# Power_And_Voltage_Shifters.net
KiCad netlist of a schematic drawn in Altium Designer
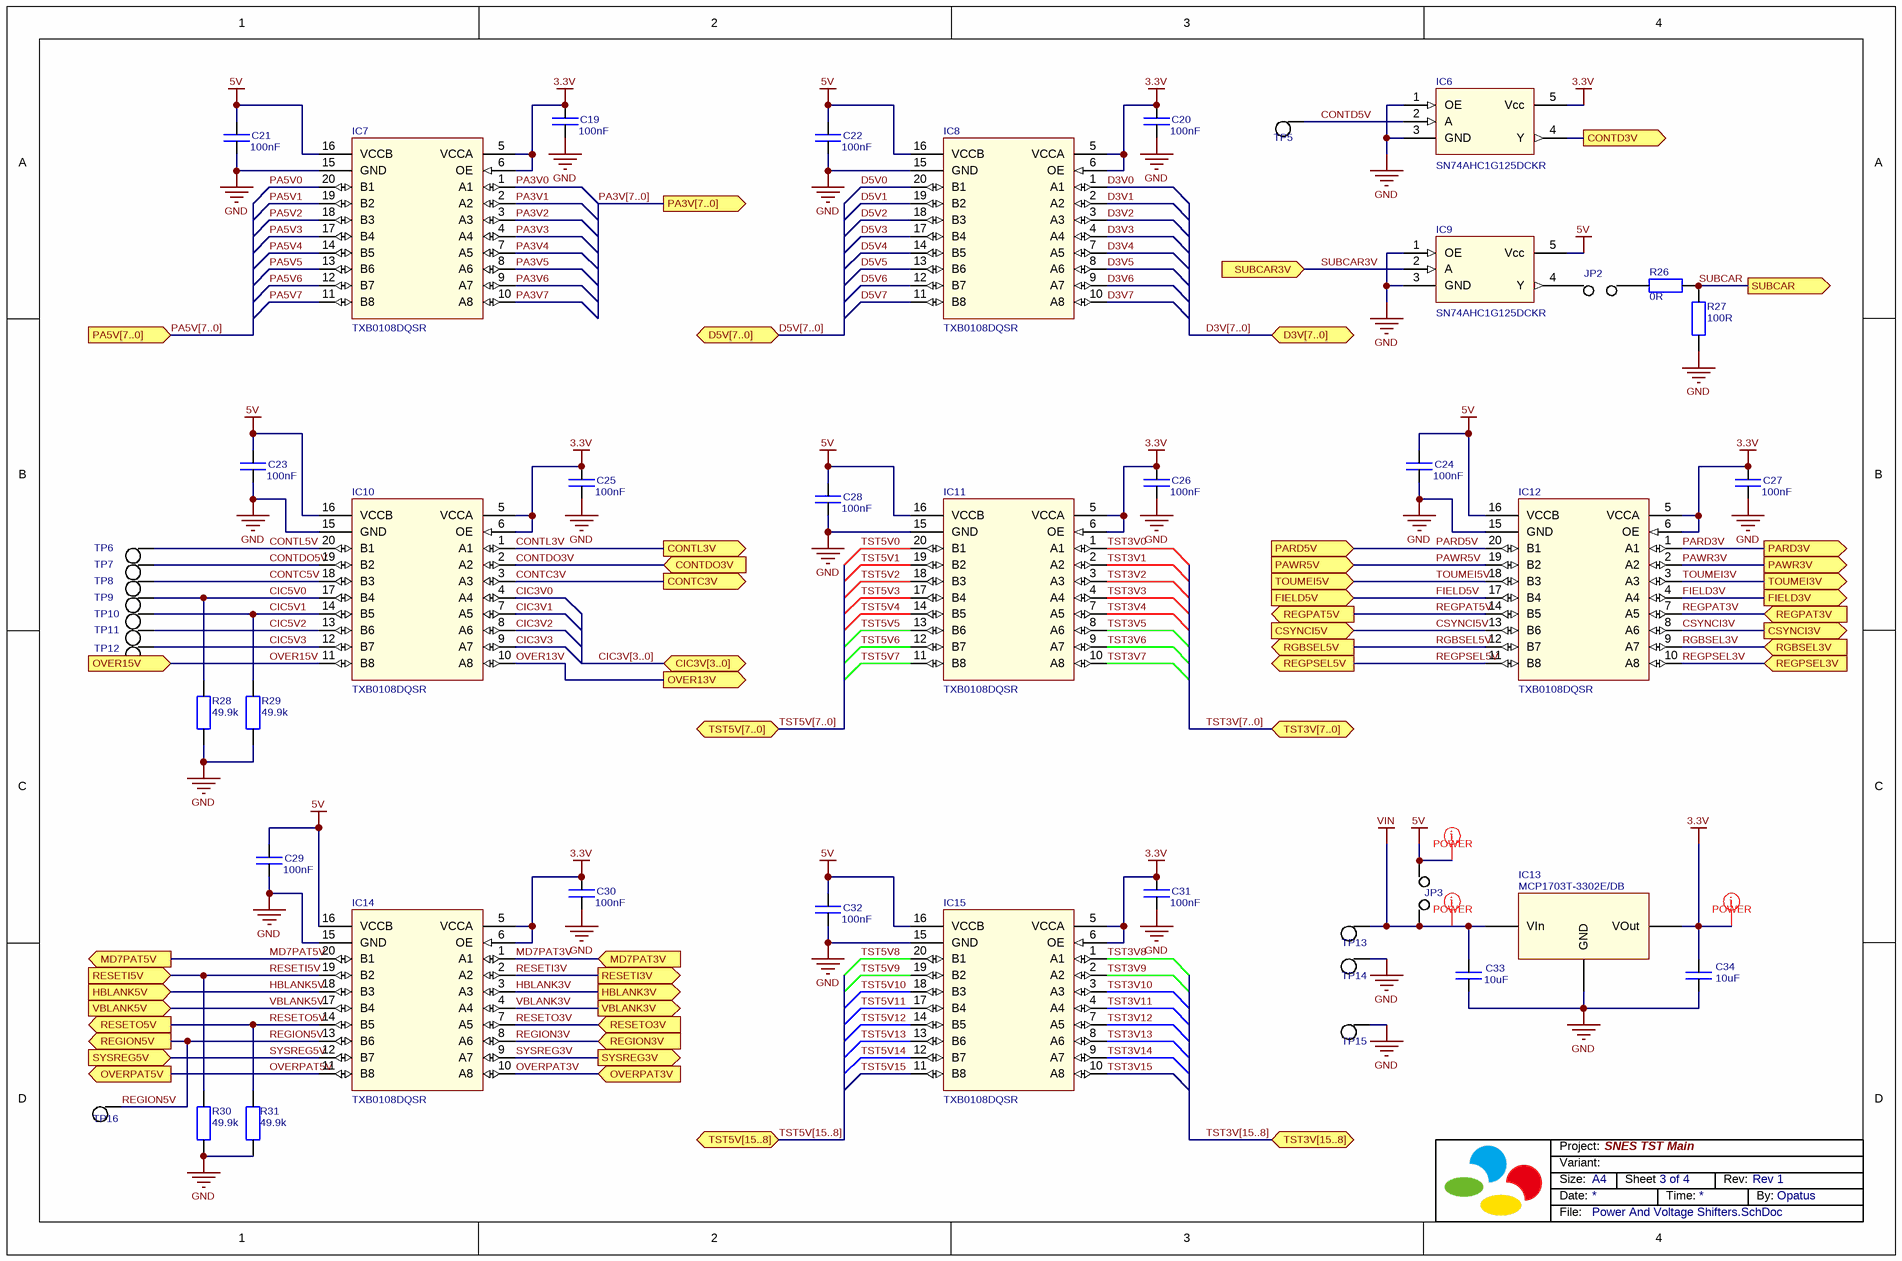
[diagram p0: Power And Voltage Shifters.SchDoc]

(export (version "E")
  (design (tool "Eeschema 10.0.6"))
  (components
    (comp (ref "C19")
      (value "100nF")
      (footprint "Cap_0402_Chip")
      (fields
        (field (name "TOLERANCE") "±20%")
        (field (name "Comment") "Ceramic Capacitor 100nF 10V ±20% X7R 0402")
      )
      (libsource (lib "PCB") (part "Capacitor"))
    )
    (comp (ref "C20")
      (value "100nF")
      (footprint "Cap_0402_Chip")
      (fields
        (field (name "TOLERANCE") "±20%")
        (field (name "Comment") "Ceramic Capacitor 100nF 10V ±20% X7R 0402")
      )
      (libsource (lib "PCB") (part "Capacitor"))
    )
    (comp (ref "C21")
      (value "100nF")
      (footprint "Cap_0402_Chip")
      (fields
        (field (name "TOLERANCE") "±20%")
        (field (name "Comment") "Ceramic Capacitor 100nF 10V ±20% X7R 0402")
      )
      (libsource (lib "PCB") (part "Capacitor"))
    )
    (comp (ref "C22")
      (value "100nF")
      (footprint "Cap_0402_Chip")
      (fields
        (field (name "TOLERANCE") "±20%")
        (field (name "Comment") "Ceramic Capacitor 100nF 10V ±20% X7R 0402")
      )
      (libsource (lib "PCB") (part "Capacitor"))
    )
    (comp (ref "C23")
      (value "100nF")
      (footprint "Cap_0402_Chip")
      (fields
        (field (name "TOLERANCE") "±20%")
        (field (name "Comment") "Ceramic Capacitor 100nF 10V ±20% X7R 0402")
      )
      (libsource (lib "PCB") (part "Capacitor"))
    )
    (comp (ref "C24")
      (value "100nF")
      (footprint "Cap_0402_Chip")
      (fields
        (field (name "TOLERANCE") "±20%")
        (field (name "Comment") "Ceramic Capacitor 100nF 10V ±20% X7R 0402")
      )
      (libsource (lib "PCB") (part "Capacitor"))
    )
    (comp (ref "C25")
      (value "100nF")
      (footprint "Cap_0402_Chip")
      (fields
        (field (name "TOLERANCE") "±20%")
        (field (name "Comment") "Ceramic Capacitor 100nF 10V ±20% X7R 0402")
      )
      (libsource (lib "PCB") (part "Capacitor"))
    )
    (comp (ref "C26")
      (value "100nF")
      (footprint "Cap_0402_Chip")
      (fields
        (field (name "TOLERANCE") "±20%")
        (field (name "Comment") "Ceramic Capacitor 100nF 10V ±20% X7R 0402")
      )
      (libsource (lib "PCB") (part "Capacitor"))
    )
    (comp (ref "C27")
      (value "100nF")
      (footprint "Cap_0402_Chip")
      (fields
        (field (name "TOLERANCE") "±20%")
        (field (name "Comment") "Ceramic Capacitor 100nF 10V ±20% X7R 0402")
      )
      (libsource (lib "PCB") (part "Capacitor"))
    )
    (comp (ref "C28")
      (value "100nF")
      (footprint "Cap_0402_Chip")
      (fields
        (field (name "TOLERANCE") "±20%")
        (field (name "Comment") "Ceramic Capacitor 100nF 10V ±20% X7R 0402")
      )
      (libsource (lib "PCB") (part "Capacitor"))
    )
    (comp (ref "C29")
      (value "100nF")
      (footprint "Cap_0402_Chip")
      (fields
        (field (name "TOLERANCE") "±20%")
        (field (name "Comment") "Ceramic Capacitor 100nF 10V ±20% X7R 0402")
      )
      (libsource (lib "PCB") (part "Capacitor"))
    )
    (comp (ref "C30")
      (value "100nF")
      (footprint "Cap_0402_Chip")
      (fields
        (field (name "TOLERANCE") "±20%")
        (field (name "Comment") "Ceramic Capacitor 100nF 10V ±20% X7R 0402")
      )
      (libsource (lib "PCB") (part "Capacitor"))
    )
    (comp (ref "C31")
      (value "100nF")
      (footprint "Cap_0402_Chip")
      (fields
        (field (name "TOLERANCE") "±20%")
        (field (name "Comment") "Ceramic Capacitor 100nF 10V ±20% X7R 0402")
      )
      (libsource (lib "PCB") (part "Capacitor"))
    )
    (comp (ref "C32")
      (value "100nF")
      (footprint "Cap_0402_Chip")
      (fields
        (field (name "TOLERANCE") "±20%")
        (field (name "Comment") "Ceramic Capacitor 100nF 10V ±20% X7R 0402")
      )
      (libsource (lib "PCB") (part "Capacitor"))
    )
    (comp (ref "C33")
      (value "10uF")
      (footprint "Cap_1206_Chip")
      (fields
        (field (name "TOLERANCE") "±20%")
        (field (name "Comment") "Ceramic Capacitor 10uF 25V ±20% X7R 1206")
      )
      (libsource (lib "PCB") (part "Capacitor"))
    )
    (comp (ref "C34")
      (value "10uF")
      (footprint "Cap_0805_Chip")
      (fields
        (field (name "TOLERANCE") "±20%")
        (field (name "Comment") "Ceramic Capacitor 10uF 10V ±20% X7R 0805")
      )
      (libsource (lib "PCB") (part "Capacitor"))
    )
    (comp (ref "IC6")
      (value "SN74AHC1G125")
      (footprint "SC70")
      (description "Non-inverting buffer")
      (fields (field (name "MANUFACTURER_PART_NUMBER") "SN74AHC1G125DCKR"))
      (libsource (lib "PCB") (part "SN74AHC1G125"))
    )
    (comp (ref "IC7")
      (value "TXB0108DQSR")
      (footprint "SON20")
      (description "8-bit level shifter")
      (fields (field (name "MANUFACTURER_PART_NUMBER") "TXB0108DQSR"))
      (libsource (lib "PCB") (part "TXB0108DQSR"))
    )
    (comp (ref "IC8")
      (value "TXB0108DQSR")
      (footprint "SON20")
      (description "8-bit level shifter")
      (fields (field (name "MANUFACTURER_PART_NUMBER") "TXB0108DQSR"))
      (libsource (lib "PCB") (part "TXB0108DQSR"))
    )
    (comp (ref "IC9")
      (value "SN74AHC1G125")
      (footprint "SC70")
      (description "Non-inverting buffer")
      (fields (field (name "MANUFACTURER_PART_NUMBER") "SN74AHC1G125DCKR"))
      (libsource (lib "PCB") (part "SN74AHC1G125"))
    )
    (comp (ref "IC10")
      (value "TXB0108DQSR")
      (footprint "SON20")
      (description "8-bit level shifter")
      (fields (field (name "MANUFACTURER_PART_NUMBER") "TXB0108DQSR"))
      (libsource (lib "PCB") (part "TXB0108DQSR"))
    )
    (comp (ref "IC11")
      (value "TXB0108DQSR")
      (footprint "SON20")
      (description "8-bit level shifter")
      (fields (field (name "MANUFACTURER_PART_NUMBER") "TXB0108DQSR"))
      (libsource (lib "PCB") (part "TXB0108DQSR"))
    )
    (comp (ref "IC12")
      (value "TXB0108DQSR")
      (footprint "SON20")
      (description "8-bit level shifter")
      (fields (field (name "MANUFACTURER_PART_NUMBER") "TXB0108DQSR"))
      (libsource (lib "PCB") (part "TXB0108DQSR"))
    )
    (comp (ref "IC13")
      (value "MCP1703T")
      (footprint "SOT223-3")
      (description "3.3V Regulator")
      (fields (field (name "MANUFACTURER_PART_NUMBER") "MCP1703T-3302E/DB"))
      (libsource (lib "PCB") (part "MCP1703 SOT223"))
    )
    (comp (ref "IC14")
      (value "TXB0108DQSR")
      (footprint "SON20")
      (description "8-bit level shifter")
      (fields (field (name "MANUFACTURER_PART_NUMBER") "TXB0108DQSR"))
      (libsource (lib "PCB") (part "TXB0108DQSR"))
    )
    (comp (ref "IC15")
      (value "TXB0108DQSR")
      (footprint "SON20")
      (description "8-bit level shifter")
      (fields (field (name "MANUFACTURER_PART_NUMBER") "TXB0108DQSR"))
      (libsource (lib "PCB") (part "TXB0108DQSR"))
    )
    (comp (ref "JP2") (value "Jumper") (footprint "Jumper") (libsource (lib "PCB") (part "Jumper")))
    (comp (ref "JP3") (value "Jumper") (footprint "Jumper Big") (libsource (lib "PCB") (part "Jumper")))
    (comp (ref "R26")
      (value "0R")
      (footprint "Res_0603_Chip")
      (fields (field (name "TOLERANCE") "±1%") (field (name "Comment") "Resistor 0R 0603 ±1%"))
      (libsource (lib "") (part "R_1"))
    )
    (comp (ref "R27")
      (value "100R")
      (footprint "Res_0603_Chip")
      (fields (field (name "TOLERANCE") "±1%") (field (name "Comment") "Resistor 100R 0603 ±1%"))
      (libsource (lib "PCB") (part "R"))
    )
    (comp (ref "R28")
      (value "49.9k")
      (footprint "Res_0402_Chip")
      (fields (field (name "TOLERANCE") "±1%") (field (name "Comment") "Resistor 49.9k 0402 ±1%"))
      (libsource (lib "") (part "R_2"))
    )
    (comp (ref "R29")
      (value "49.9k")
      (footprint "Res_0402_Chip")
      (fields (field (name "TOLERANCE") "±1%") (field (name "Comment") "Resistor 49.9k 0402 ±1%"))
      (libsource (lib "") (part "R_2"))
    )
    (comp (ref "R30")
      (value "49.9k")
      (footprint "Res_0402_Chip")
      (fields (field (name "TOLERANCE") "±1%") (field (name "Comment") "Resistor 49.9k 0402 ±1%"))
      (libsource (lib "PCB") (part "R"))
    )
    (comp (ref "R31")
      (value "49.9k")
      (footprint "Res_0402_Chip")
      (fields (field (name "TOLERANCE") "±1%") (field (name "Comment") "Resistor 49.9k 0402 ±1%"))
      (libsource (lib "") (part "R_2"))
    )
    (comp (ref "TP5")
      (value "Pin Connector")
      (footprint "Pin Connector Small")
      (libsource (lib "PCB") (part "Pin Connector"))
    )
    (comp (ref "TP6")
      (value "Pin Connector")
      (footprint "Pin Connector Small")
      (libsource (lib "PCB") (part "Pin Connector"))
    )
    (comp (ref "TP7")
      (value "Pin Connector")
      (footprint "Pin Connector Small")
      (libsource (lib "PCB") (part "Pin Connector"))
    )
    (comp (ref "TP8")
      (value "Pin Connector")
      (footprint "Pin Connector Small")
      (libsource (lib "PCB") (part "Pin Connector"))
    )
    (comp (ref "TP9")
      (value "Pin Connector")
      (footprint "Pin Connector Small")
      (libsource (lib "PCB") (part "Pin Connector"))
    )
    (comp (ref "TP10")
      (value "Pin Connector")
      (footprint "Pin Connector Small")
      (libsource (lib "PCB") (part "Pin Connector"))
    )
    (comp (ref "TP11")
      (value "Pin Connector")
      (footprint "Pin Connector Small")
      (libsource (lib "PCB") (part "Pin Connector"))
    )
    (comp (ref "TP12")
      (value "Pin Connector")
      (footprint "Pin Connector Small")
      (libsource (lib "PCB") (part "Pin Connector"))
    )
    (comp (ref "TP13")
      (value "Pin Connector")
      (footprint "Pin Connector Small")
      (libsource (lib "PCB") (part "Pin Connector"))
    )
    (comp (ref "TP14")
      (value "Pin Connector")
      (footprint "Pin Connector Small")
      (libsource (lib "PCB") (part "Pin Connector"))
    )
    (comp (ref "TP15")
      (value "Pin Connector")
      (footprint "Pin Connector Small")
      (libsource (lib "PCB") (part "Pin Connector"))
    )
    (comp (ref "TP16")
      (value "Pin Connector")
      (footprint "Pin Connector Small")
      (libsource (lib "PCB") (part "Pin Connector"))
    )
  )
  (nets
    (net (code "1") (name "/CIC3V0") (class "Default")
      (node (ref "IC10") (pin "4") (pinfunction "A4_4") (pintype "bidirectional"))
    )
    (net (code "2") (name "/CIC3V1") (class "Default")
      (node (ref "IC10") (pin "7") (pinfunction "A5_7") (pintype "bidirectional"))
    )
    (net (code "3") (name "/CIC3V2") (class "Default")
      (node (ref "IC10") (pin "8") (pinfunction "A6_8") (pintype "bidirectional"))
    )
    (net (code "4") (name "/CIC3V3") (class "Default")
      (node (ref "IC10") (pin "9") (pinfunction "A7_9") (pintype "bidirectional"))
    )
    (net (code "6") (name "/CIC5V0") (class "Default")
      (node (ref "IC10") (pin "17") (pinfunction "B4_17") (pintype "bidirectional"))
      (node (ref "R28") (pin "2") (pintype "passive"))
      (node (ref "TP9") (pin "1") (pinfunction "0_1") (pintype "passive"))
    )
    (net (code "7") (name "/CIC5V1") (class "Default")
      (node (ref "IC10") (pin "14") (pinfunction "B5_14") (pintype "bidirectional"))
      (node (ref "R29") (pin "2") (pintype "passive"))
      (node (ref "TP10") (pin "1") (pinfunction "0_1") (pintype "passive"))
    )
    (net (code "8") (name "/CIC5V2") (class "Default")
      (node (ref "IC10") (pin "13") (pinfunction "B6_13") (pintype "bidirectional"))
      (node (ref "TP11") (pin "1") (pinfunction "0_1") (pintype "passive"))
    )
    (net (code "9") (name "/CIC5V3") (class "Default")
      (node (ref "IC10") (pin "12") (pinfunction "B7_12") (pintype "bidirectional"))
      (node (ref "TP12") (pin "1") (pinfunction "0_1") (pintype "passive"))
    )
    (net (code "10") (name "/CONTC3V") (class "Default")
      (node (ref "IC10") (pin "3") (pinfunction "A3_3") (pintype "bidirectional"))
    )
    (net (code "11") (name "/CONTC5V") (class "Default")
      (node (ref "IC10") (pin "18") (pinfunction "B3_18") (pintype "bidirectional"))
      (node (ref "TP8") (pin "1") (pinfunction "0_1") (pintype "passive"))
    )
    (net (code "12") (name "/CONTD3V") (class "Default")
      (node (ref "IC6") (pin "4") (pinfunction "Y_4") (pintype "output"))
    )
    (net (code "13") (name "/CONTD5V") (class "Default")
      (node (ref "IC6") (pin "2") (pinfunction "A_2") (pintype "input"))
      (node (ref "TP5") (pin "1") (pinfunction "0_1") (pintype "passive"))
    )
    (net (code "14") (name "/CONTDO3V") (class "Default")
      (node (ref "IC10") (pin "2") (pinfunction "A2_2") (pintype "bidirectional"))
    )
    (net (code "15") (name "/CONTDO5V") (class "Default")
      (node (ref "IC10") (pin "19") (pinfunction "B2_19") (pintype "bidirectional"))
      (node (ref "TP7") (pin "1") (pinfunction "0_1") (pintype "passive"))
    )
    (net (code "16") (name "/CONTL3V") (class "Default")
      (node (ref "IC10") (pin "1") (pinfunction "A1_1") (pintype "bidirectional"))
    )
    (net (code "17") (name "/CONTL5V") (class "Default")
      (node (ref "IC10") (pin "20") (pinfunction "B1_20") (pintype "bidirectional"))
      (node (ref "TP6") (pin "1") (pinfunction "0_1") (pintype "passive"))
    )
    (net (code "18") (name "/CSYNCI3V") (class "Default")
      (node (ref "IC12") (pin "8") (pinfunction "A6_8") (pintype "bidirectional"))
    )
    (net (code "19") (name "/CSYNCI5V") (class "Default")
      (node (ref "IC12") (pin "13") (pinfunction "B6_13") (pintype "bidirectional"))
    )
    (net (code "20") (name "/D3V0") (class "Default")
      (node (ref "IC8") (pin "1") (pinfunction "A1_1") (pintype "bidirectional"))
    )
    (net (code "21") (name "/D3V1") (class "Default")
      (node (ref "IC8") (pin "2") (pinfunction "A2_2") (pintype "bidirectional"))
    )
    (net (code "22") (name "/D3V2") (class "Default")
      (node (ref "IC8") (pin "3") (pinfunction "A3_3") (pintype "bidirectional"))
    )
    (net (code "23") (name "/D3V3") (class "Default")
      (node (ref "IC8") (pin "4") (pinfunction "A4_4") (pintype "bidirectional"))
    )
    (net (code "24") (name "/D3V4") (class "Default")
      (node (ref "IC8") (pin "7") (pinfunction "A5_7") (pintype "bidirectional"))
    )
    (net (code "25") (name "/D3V5") (class "Default")
      (node (ref "IC8") (pin "8") (pinfunction "A6_8") (pintype "bidirectional"))
    )
    (net (code "26") (name "/D3V6") (class "Default")
      (node (ref "IC8") (pin "9") (pinfunction "A7_9") (pintype "bidirectional"))
    )
    (net (code "27") (name "/D3V7") (class "Default")
      (node (ref "IC8") (pin "10") (pinfunction "A8_10") (pintype "bidirectional"))
    )
    (net (code "29") (name "/D5V0") (class "Default")
      (node (ref "IC8") (pin "20") (pinfunction "B1_20") (pintype "bidirectional"))
    )
    (net (code "30") (name "/D5V1") (class "Default")
      (node (ref "IC8") (pin "19") (pinfunction "B2_19") (pintype "bidirectional"))
    )
    (net (code "31") (name "/D5V2") (class "Default")
      (node (ref "IC8") (pin "18") (pinfunction "B3_18") (pintype "bidirectional"))
    )
    (net (code "32") (name "/D5V3") (class "Default")
      (node (ref "IC8") (pin "17") (pinfunction "B4_17") (pintype "bidirectional"))
    )
    (net (code "33") (name "/D5V4") (class "Default")
      (node (ref "IC8") (pin "14") (pinfunction "B5_14") (pintype "bidirectional"))
    )
    (net (code "34") (name "/D5V5") (class "Default")
      (node (ref "IC8") (pin "13") (pinfunction "B6_13") (pintype "bidirectional"))
    )
    (net (code "35") (name "/D5V6") (class "Default")
      (node (ref "IC8") (pin "12") (pinfunction "B7_12") (pintype "bidirectional"))
    )
    (net (code "36") (name "/D5V7") (class "Default")
      (node (ref "IC8") (pin "11") (pinfunction "B8_11") (pintype "bidirectional"))
    )
    (net (code "38") (name "/FIELD3V") (class "Default")
      (node (ref "IC12") (pin "4") (pinfunction "A4_4") (pintype "bidirectional"))
    )
    (net (code "39") (name "/FIELD5V") (class "Default")
      (node (ref "IC12") (pin "17") (pinfunction "B4_17") (pintype "bidirectional"))
    )
    (net (code "40") (name "/HBLANK3V") (class "Default")
      (node (ref "IC14") (pin "3") (pinfunction "A3_3") (pintype "bidirectional"))
    )
    (net (code "41") (name "/HBLANK5V") (class "Default")
      (node (ref "IC14") (pin "18") (pinfunction "B3_18") (pintype "bidirectional"))
    )
    (net (code "42") (name "/MD7PAT3V") (class "Default")
      (node (ref "IC14") (pin "1") (pinfunction "A1_1") (pintype "bidirectional"))
    )
    (net (code "43") (name "/MD7PAT5V") (class "Default")
      (node (ref "IC14") (pin "20") (pinfunction "B1_20") (pintype "bidirectional"))
    )
    (net (code "44") (name "/OVER13V") (class "Default")
      (node (ref "IC10") (pin "10") (pinfunction "A8_10") (pintype "bidirectional"))
    )
    (net (code "45") (name "/OVER15V") (class "Default")
      (node (ref "IC10") (pin "11") (pinfunction "B8_11") (pintype "bidirectional"))
    )
    (net (code "46") (name "/OVERPAT3V") (class "Default")
      (node (ref "IC14") (pin "10") (pinfunction "A8_10") (pintype "bidirectional"))
    )
    (net (code "47") (name "/OVERPAT5V") (class "Default")
      (node (ref "IC14") (pin "11") (pinfunction "B8_11") (pintype "bidirectional"))
    )
    (net (code "48") (name "/PA3V0") (class "Default")
      (node (ref "IC7") (pin "1") (pinfunction "A1_1") (pintype "bidirectional"))
    )
    (net (code "49") (name "/PA3V1") (class "Default")
      (node (ref "IC7") (pin "2") (pinfunction "A2_2") (pintype "bidirectional"))
    )
    (net (code "50") (name "/PA3V2") (class "Default")
      (node (ref "IC7") (pin "3") (pinfunction "A3_3") (pintype "bidirectional"))
    )
    (net (code "51") (name "/PA3V3") (class "Default")
      (node (ref "IC7") (pin "4") (pinfunction "A4_4") (pintype "bidirectional"))
    )
    (net (code "52") (name "/PA3V4") (class "Default")
      (node (ref "IC7") (pin "7") (pinfunction "A5_7") (pintype "bidirectional"))
    )
    (net (code "53") (name "/PA3V5") (class "Default")
      (node (ref "IC7") (pin "8") (pinfunction "A6_8") (pintype "bidirectional"))
    )
    (net (code "54") (name "/PA3V6") (class "Default")
      (node (ref "IC7") (pin "9") (pinfunction "A7_9") (pintype "bidirectional"))
    )
    (net (code "55") (name "/PA3V7") (class "Default")
      (node (ref "IC7") (pin "10") (pinfunction "A8_10") (pintype "bidirectional"))
    )
    (net (code "57") (name "/PA5V0") (class "Default")
      (node (ref "IC7") (pin "20") (pinfunction "B1_20") (pintype "bidirectional"))
    )
    (net (code "58") (name "/PA5V1") (class "Default")
      (node (ref "IC7") (pin "19") (pinfunction "B2_19") (pintype "bidirectional"))
    )
    (net (code "59") (name "/PA5V2") (class "Default")
      (node (ref "IC7") (pin "18") (pinfunction "B3_18") (pintype "bidirectional"))
    )
    (net (code "60") (name "/PA5V3") (class "Default")
      (node (ref "IC7") (pin "17") (pinfunction "B4_17") (pintype "bidirectional"))
    )
    (net (code "61") (name "/PA5V4") (class "Default")
      (node (ref "IC7") (pin "14") (pinfunction "B5_14") (pintype "bidirectional"))
    )
    (net (code "62") (name "/PA5V5") (class "Default")
      (node (ref "IC7") (pin "13") (pinfunction "B6_13") (pintype "bidirectional"))
    )
    (net (code "63") (name "/PA5V6") (class "Default")
      (node (ref "IC7") (pin "12") (pinfunction "B7_12") (pintype "bidirectional"))
    )
    (net (code "64") (name "/PA5V7") (class "Default")
      (node (ref "IC7") (pin "11") (pinfunction "B8_11") (pintype "bidirectional"))
    )
    (net (code "66") (name "/PARD3V") (class "Default")
      (node (ref "IC12") (pin "1") (pinfunction "A1_1") (pintype "bidirectional"))
    )
    (net (code "67") (name "/PARD5V") (class "Default")
      (node (ref "IC12") (pin "20") (pinfunction "B1_20") (pintype "bidirectional"))
    )
    (net (code "68") (name "/PAWR3V") (class "Default")
      (node (ref "IC12") (pin "2") (pinfunction "A2_2") (pintype "bidirectional"))
    )
    (net (code "69") (name "/PAWR5V") (class "Default")
      (node (ref "IC12") (pin "19") (pinfunction "B2_19") (pintype "bidirectional"))
    )
    (net (code "70") (name "/REGION3V") (class "Default")
      (node (ref "IC14") (pin "8") (pinfunction "A6_8") (pintype "bidirectional"))
    )
    (net (code "71") (name "/REGION5V") (class "Default")
      (node (ref "IC14") (pin "13") (pinfunction "B6_13") (pintype "bidirectional"))
      (node (ref "TP16") (pin "1") (pinfunction "0_1") (pintype "passive"))
    )
    (net (code "72") (name "/REGPAT3V") (class "Default")
      (node (ref "IC12") (pin "7") (pinfunction "A5_7") (pintype "bidirectional"))
    )
    (net (code "73") (name "/REGPAT5V") (class "Default")
      (node (ref "IC12") (pin "14") (pinfunction "B5_14") (pintype "bidirectional"))
    )
    (net (code "74") (name "/REGPSEL3V") (class "Default")
      (node (ref "IC12") (pin "10") (pinfunction "A8_10") (pintype "bidirectional"))
    )
    (net (code "75") (name "/REGPSEL5V") (class "Default")
      (node (ref "IC12") (pin "11") (pinfunction "B8_11") (pintype "bidirectional"))
    )
    (net (code "76") (name "/RESETI3V") (class "Default")
      (node (ref "IC14") (pin "2") (pinfunction "A2_2") (pintype "bidirectional"))
    )
    (net (code "77") (name "/RESETI5V") (class "Default")
      (node (ref "IC14") (pin "19") (pinfunction "B2_19") (pintype "bidirectional"))
      (node (ref "R30") (pin "1") (pintype "passive"))
    )
    (net (code "78") (name "/RESETO3V") (class "Default")
      (node (ref "IC14") (pin "7") (pinfunction "A5_7") (pintype "bidirectional"))
    )
    (net (code "79") (name "/RESETO5V") (class "Default")
      (node (ref "IC14") (pin "14") (pinfunction "B5_14") (pintype "bidirectional"))
      (node (ref "R31") (pin "2") (pintype "passive"))
    )
    (net (code "80") (name "/RGBSEL3V") (class "Default")
      (node (ref "IC12") (pin "9") (pinfunction "A7_9") (pintype "bidirectional"))
    )
    (net (code "81") (name "/RGBSEL5V") (class "Default")
      (node (ref "IC12") (pin "12") (pinfunction "B7_12") (pintype "bidirectional"))
    )
    (net (code "82") (name "/SUBCAR") (class "Default")
      (node (ref "R26") (pin "1") (pintype "passive"))
      (node (ref "R27") (pin "1") (pintype "passive"))
    )
    (net (code "83") (name "/SUBCAR3V") (class "Default")
      (node (ref "IC9") (pin "2") (pinfunction "A_2") (pintype "input"))
    )
    (net (code "84") (name "/SYSREG3V") (class "Default")
      (node (ref "IC14") (pin "9") (pinfunction "A7_9") (pintype "bidirectional"))
    )
    (net (code "85") (name "/SYSREG5V") (class "Default")
      (node (ref "IC14") (pin "12") (pinfunction "B7_12") (pintype "bidirectional"))
    )
    (net (code "86") (name "/TOUMEI3V") (class "Default")
      (node (ref "IC12") (pin "3") (pinfunction "A3_3") (pintype "bidirectional"))
    )
    (net (code "87") (name "/TOUMEI5V") (class "Default")
      (node (ref "IC12") (pin "18") (pinfunction "B3_18") (pintype "bidirectional"))
    )
    (net (code "88") (name "/TST3V0") (class "Default")
      (node (ref "IC11") (pin "1") (pinfunction "A1_1") (pintype "bidirectional"))
    )
    (net (code "89") (name "/TST3V1") (class "Default")
      (node (ref "IC11") (pin "2") (pinfunction "A2_2") (pintype "bidirectional"))
    )
    (net (code "90") (name "/TST3V2") (class "Default")
      (node (ref "IC11") (pin "3") (pinfunction "A3_3") (pintype "bidirectional"))
    )
    (net (code "91") (name "/TST3V3") (class "Default")
      (node (ref "IC11") (pin "4") (pinfunction "A4_4") (pintype "bidirectional"))
    )
    (net (code "92") (name "/TST3V4") (class "Default")
      (node (ref "IC11") (pin "7") (pinfunction "A5_7") (pintype "bidirectional"))
    )
    (net (code "93") (name "/TST3V5") (class "Default")
      (node (ref "IC11") (pin "8") (pinfunction "A6_8") (pintype "bidirectional"))
    )
    (net (code "94") (name "/TST3V6") (class "Default")
      (node (ref "IC11") (pin "9") (pinfunction "A7_9") (pintype "bidirectional"))
    )
    (net (code "95") (name "/TST3V7") (class "Default")
      (node (ref "IC11") (pin "10") (pinfunction "A8_10") (pintype "bidirectional"))
    )
    (net (code "96") (name "/TST3V8") (class "Default")
      (node (ref "IC15") (pin "1") (pinfunction "A1_1") (pintype "bidirectional"))
    )
    (net (code "97") (name "/TST3V9") (class "Default")
      (node (ref "IC15") (pin "2") (pinfunction "A2_2") (pintype "bidirectional"))
    )
    (net (code "98") (name "/TST3V10") (class "Default")
      (node (ref "IC15") (pin "3") (pinfunction "A3_3") (pintype "bidirectional"))
    )
    (net (code "99") (name "/TST3V11") (class "Default")
      (node (ref "IC15") (pin "4") (pinfunction "A4_4") (pintype "bidirectional"))
    )
    (net (code "100") (name "/TST3V12") (class "Default")
      (node (ref "IC15") (pin "7") (pinfunction "A5_7") (pintype "bidirectional"))
    )
    (net (code "101") (name "/TST3V13") (class "Default")
      (node (ref "IC15") (pin "8") (pinfunction "A6_8") (pintype "bidirectional"))
    )
    (net (code "102") (name "/TST3V14") (class "Default")
      (node (ref "IC15") (pin "9") (pinfunction "A7_9") (pintype "bidirectional"))
    )
    (net (code "103") (name "/TST3V15") (class "Default")
      (node (ref "IC15") (pin "10") (pinfunction "A8_10") (pintype "bidirectional"))
    )
    (net (code "106") (name "/TST5V0") (class "Default")
      (node (ref "IC11") (pin "20") (pinfunction "B1_20") (pintype "bidirectional"))
    )
    (net (code "107") (name "/TST5V1") (class "Default")
      (node (ref "IC11") (pin "19") (pinfunction "B2_19") (pintype "bidirectional"))
    )
    (net (code "108") (name "/TST5V2") (class "Default")
      (node (ref "IC11") (pin "18") (pinfunction "B3_18") (pintype "bidirectional"))
    )
    (net (code "109") (name "/TST5V3") (class "Default")
      (node (ref "IC11") (pin "17") (pinfunction "B4_17") (pintype "bidirectional"))
    )
    (net (code "110") (name "/TST5V4") (class "Default")
      (node (ref "IC11") (pin "14") (pinfunction "B5_14") (pintype "bidirectional"))
    )
    (net (code "111") (name "/TST5V5") (class "Default")
      (node (ref "IC11") (pin "13") (pinfunction "B6_13") (pintype "bidirectional"))
    )
    (net (code "112") (name "/TST5V6") (class "Default")
      (node (ref "IC11") (pin "12") (pinfunction "B7_12") (pintype "bidirectional"))
    )
    (net (code "113") (name "/TST5V7") (class "Default")
      (node (ref "IC11") (pin "11") (pinfunction "B8_11") (pintype "bidirectional"))
    )
    (net (code "114") (name "/TST5V8") (class "Default")
      (node (ref "IC15") (pin "20") (pinfunction "B1_20") (pintype "bidirectional"))
    )
    (net (code "115") (name "/TST5V9") (class "Default")
      (node (ref "IC15") (pin "19") (pinfunction "B2_19") (pintype "bidirectional"))
    )
    (net (code "116") (name "/TST5V10") (class "Default")
      (node (ref "IC15") (pin "18") (pinfunction "B3_18") (pintype "bidirectional"))
    )
    (net (code "117") (name "/TST5V11") (class "Default")
      (node (ref "IC15") (pin "17") (pinfunction "B4_17") (pintype "bidirectional"))
    )
    (net (code "118") (name "/TST5V12") (class "Default")
      (node (ref "IC15") (pin "14") (pinfunction "B5_14") (pintype "bidirectional"))
    )
    (net (code "119") (name "/TST5V13") (class "Default")
      (node (ref "IC15") (pin "13") (pinfunction "B6_13") (pintype "bidirectional"))
    )
    (net (code "120") (name "/TST5V14") (class "Default")
      (node (ref "IC15") (pin "12") (pinfunction "B7_12") (pintype "bidirectional"))
    )
    (net (code "121") (name "/TST5V15") (class "Default")
      (node (ref "IC15") (pin "11") (pinfunction "B8_11") (pintype "bidirectional"))
    )
    (net (code "124") (name "/VBLANK3V") (class "Default")
      (node (ref "IC14") (pin "4") (pinfunction "A4_4") (pintype "bidirectional"))
    )
    (net (code "125") (name "/VBLANK5V") (class "Default")
      (node (ref "IC14") (pin "17") (pinfunction "B4_17") (pintype "bidirectional"))
    )
    (net (code "126") (name "3.3V") (class "Default")
      (node (ref "C19") (pin "1") (pintype "passive"))
      (node (ref "C20") (pin "1") (pintype "passive"))
      (node (ref "C25") (pin "1") (pintype "passive"))
      (node (ref "C26") (pin "1") (pintype "passive"))
      (node (ref "C27") (pin "1") (pintype "passive"))
      (node (ref "C30") (pin "1") (pintype "passive"))
      (node (ref "C31") (pin "1") (pintype "passive"))
      (node (ref "C34") (pin "2") (pintype "passive"))
      (node (ref "IC10") (pin "5") (pinfunction "VCCA_5") (pintype "power_in"))
      (node (ref "IC10") (pin "6") (pinfunction "OE_6") (pintype "input"))
      (node (ref "IC11") (pin "5") (pinfunction "VCCA_5") (pintype "power_in"))
      (node (ref "IC11") (pin "6") (pinfunction "OE_6") (pintype "input"))
      (node (ref "IC12") (pin "5") (pinfunction "VCCA_5") (pintype "power_in"))
      (node (ref "IC12") (pin "6") (pinfunction "OE_6") (pintype "input"))
      (node (ref "IC13") (pin "3") (pinfunction "VOut_3") (pintype "passive"))
      (node (ref "IC14") (pin "5") (pinfunction "VCCA_5") (pintype "power_in"))
      (node (ref "IC14") (pin "6") (pinfunction "OE_6") (pintype "input"))
      (node (ref "IC15") (pin "5") (pinfunction "VCCA_5") (pintype "power_in"))
      (node (ref "IC15") (pin "6") (pinfunction "OE_6") (pintype "input"))
      (node (ref "IC6") (pin "5") (pinfunction "Vcc_5") (pintype "power_in"))
      (node (ref "IC7") (pin "5") (pinfunction "VCCA_5") (pintype "power_in"))
      (node (ref "IC7") (pin "6") (pinfunction "OE_6") (pintype "input"))
      (node (ref "IC8") (pin "5") (pinfunction "VCCA_5") (pintype "power_in"))
      (node (ref "IC8") (pin "6") (pinfunction "OE_6") (pintype "input"))
    )
    (net (code "127") (name "5V") (class "Default")
      (node (ref "C21") (pin "1") (pintype "passive"))
      (node (ref "C22") (pin "1") (pintype "passive"))
      (node (ref "C23") (pin "1") (pintype "passive"))
      (node (ref "C24") (pin "1") (pintype "passive"))
      (node (ref "C28") (pin "1") (pintype "passive"))
      (node (ref "C29") (pin "1") (pintype "passive"))
      (node (ref "C32") (pin "1") (pintype "passive"))
      (node (ref "IC10") (pin "16") (pinfunction "VCCB_16") (pintype "power_in"))
      (node (ref "IC11") (pin "16") (pinfunction "VCCB_16") (pintype "power_in"))
      (node (ref "IC12") (pin "16") (pinfunction "VCCB_16") (pintype "power_in"))
      (node (ref "IC14") (pin "16") (pinfunction "VCCB_16") (pintype "power_in"))
      (node (ref "IC15") (pin "16") (pinfunction "VCCB_16") (pintype "power_in"))
      (node (ref "IC7") (pin "16") (pinfunction "VCCB_16") (pintype "power_in"))
      (node (ref "IC8") (pin "16") (pinfunction "VCCB_16") (pintype "power_in"))
      (node (ref "IC9") (pin "5") (pinfunction "Vcc_5") (pintype "power_in"))
      (node (ref "JP3") (pin "1") (pinfunction "0_1") (pintype "passive"))
    )
    (net (code "128") (name "GND") (class "Default")
      (node (ref "C19") (pin "2") (pintype "passive"))
      (node (ref "C20") (pin "2") (pintype "passive"))
      (node (ref "C21") (pin "2") (pintype "passive"))
      (node (ref "C22") (pin "2") (pintype "passive"))
      (node (ref "C23") (pin "2") (pintype "passive"))
      (node (ref "C24") (pin "2") (pintype "passive"))
      (node (ref "C25") (pin "2") (pintype "passive"))
      (node (ref "C26") (pin "2") (pintype "passive"))
      (node (ref "C27") (pin "2") (pintype "passive"))
      (node (ref "C28") (pin "2") (pintype "passive"))
      (node (ref "C29") (pin "2") (pintype "passive"))
      (node (ref "C30") (pin "2") (pintype "passive"))
      (node (ref "C31") (pin "2") (pintype "passive"))
      (node (ref "C32") (pin "2") (pintype "passive"))
      (node (ref "C33") (pin "1") (pintype "passive"))
      (node (ref "C34") (pin "1") (pintype "passive"))
      (node (ref "IC10") (pin "15") (pinfunction "GND_15") (pintype "power_in"))
      (node (ref "IC11") (pin "15") (pinfunction "GND_15") (pintype "power_in"))
      (node (ref "IC12") (pin "15") (pinfunction "GND_15") (pintype "power_in"))
      (node (ref "IC13") (pin "2") (pinfunction "GND_2") (pintype "passive"))
      (node (ref "IC14") (pin "15") (pinfunction "GND_15") (pintype "power_in"))
      (node (ref "IC15") (pin "15") (pinfunction "GND_15") (pintype "power_in"))
      (node (ref "IC6") (pin "1") (pinfunction "OE_1") (pintype "input"))
      (node (ref "IC6") (pin "3") (pinfunction "GND_3") (pintype "power_in"))
      (node (ref "IC7") (pin "15") (pinfunction "GND_15") (pintype "power_in"))
      (node (ref "IC8") (pin "15") (pinfunction "GND_15") (pintype "power_in"))
      (node (ref "IC9") (pin "1") (pinfunction "OE_1") (pintype "input"))
      (node (ref "IC9") (pin "3") (pinfunction "GND_3") (pintype "power_in"))
      (node (ref "R27") (pin "2") (pintype "passive"))
      (node (ref "R28") (pin "1") (pintype "passive"))
      (node (ref "R29") (pin "1") (pintype "passive"))
      (node (ref "R30") (pin "2") (pintype "passive"))
      (node (ref "R31") (pin "1") (pintype "passive"))
      (node (ref "TP14") (pin "1") (pinfunction "0_1") (pintype "passive"))
      (node (ref "TP15") (pin "1") (pinfunction "0_1") (pintype "passive"))
    )
    (net (code "129") (name "Net-(IC9-Y)") (class "Default")
      (node (ref "IC9") (pin "4") (pinfunction "Y_4") (pintype "output"))
      (node (ref "JP2") (pin "2") (pinfunction "0_2") (pintype "passive"))
    )
    (net (code "130") (name "Net-(JP2-0-Pad1)") (class "Default")
      (node (ref "JP2") (pin "1") (pinfunction "0_1") (pintype "passive"))
      (node (ref "R26") (pin "2") (pintype "passive"))
    )
    (net (code "131") (name "VIN") (class "Default")
      (node (ref "C33") (pin "2") (pintype "passive"))
      (node (ref "IC13") (pin "1") (pinfunction "VIn_1") (pintype "passive"))
      (node (ref "JP3") (pin "2") (pinfunction "0_2") (pintype "passive"))
      (node (ref "TP13") (pin "1") (pinfunction "0_1") (pintype "passive"))
    )
  )
)
